# SH6_-_LOAD_MONITORING_1.net
KiCad netlist of a schematic drawn in Altium Designer
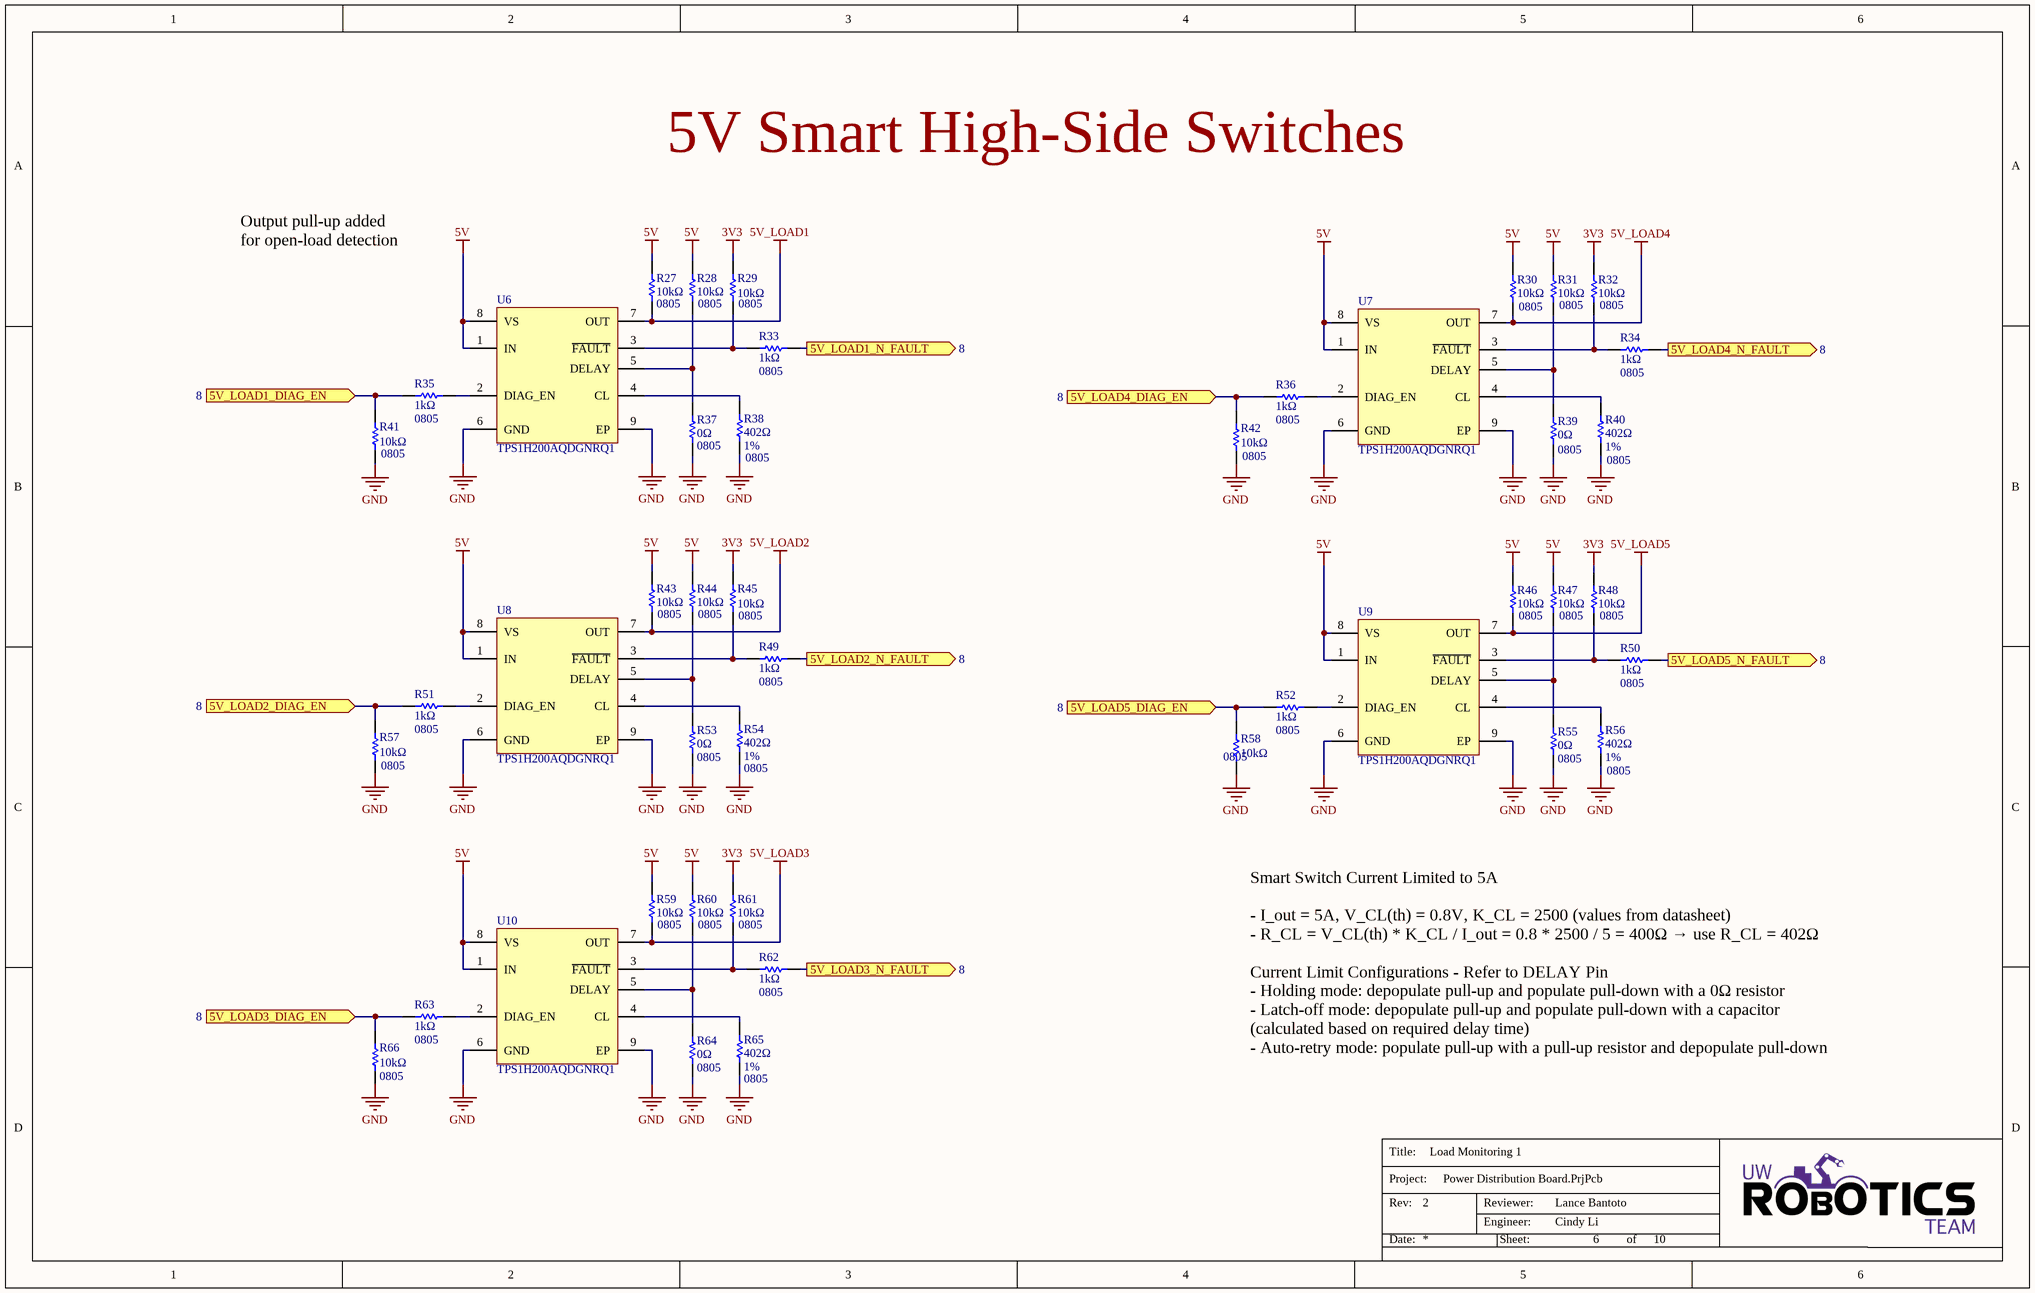
[diagram p0: SH6 - LOAD MONITORING 1.SchDoc]

(export (version "E")
  (design (tool "Eeschema 10.0.6"))
  (components
    (comp (ref "R27")
      (value "10kΩ")
      (footprint "RESC0805")
      (description "RES 10K OHM 5% 1/8W 0805")
      (fields
        (field (name "LCSC PART #") "C17414")
        (field (name "PACKAGE/FOOTPRINT") "0805")
        (field (name "Comment") "RES_10kΩ_0805_5%")
      )
      (libsource (lib "UWRT_Schematic_Library_2020") (part "RES_10kΩ_0805_5%"))
    )
    (comp (ref "R28")
      (value "10kΩ")
      (footprint "RESC0805")
      (description "RES 10K OHM 5% 1/8W 0805")
      (fields
        (field (name "LCSC PART #") "C17414")
        (field (name "PACKAGE/FOOTPRINT") "0805")
        (field (name "Comment") "RES_10kΩ_0805_5%")
      )
      (libsource (lib "UWRT_Schematic_Library_2020") (part "RES_10kΩ_0805_5%"))
    )
    (comp (ref "R29")
      (value "10kΩ")
      (footprint "RESC0805")
      (description "RES 10K OHM 5% 1/8W 0805")
      (fields
        (field (name "LCSC PART #") "C17414")
        (field (name "PACKAGE/FOOTPRINT") "0805")
        (field (name "Comment") "RES_10kΩ_0805_5%")
      )
      (libsource (lib "UWRT_Schematic_Library_2020") (part "RES_10kΩ_0805_5%"))
    )
    (comp (ref "R30")
      (value "10kΩ")
      (footprint "RESC0805")
      (description "RES 10K OHM 5% 1/8W 0805")
      (fields
        (field (name "LCSC PART #") "C17414")
        (field (name "PACKAGE/FOOTPRINT") "0805")
        (field (name "Comment") "RES_10kΩ_0805_5%")
      )
      (libsource (lib "UWRT_Schematic_Library_2020") (part "RES_10kΩ_0805_5%"))
    )
    (comp (ref "R31")
      (value "10kΩ")
      (footprint "RESC0805")
      (description "RES 10K OHM 5% 1/8W 0805")
      (fields
        (field (name "LCSC PART #") "C17414")
        (field (name "PACKAGE/FOOTPRINT") "0805")
        (field (name "Comment") "RES_10kΩ_0805_5%")
      )
      (libsource (lib "UWRT_Schematic_Library_2020") (part "RES_10kΩ_0805_5%"))
    )
    (comp (ref "R32")
      (value "10kΩ")
      (footprint "RESC0805")
      (description "RES 10K OHM 5% 1/8W 0805")
      (fields
        (field (name "LCSC PART #") "C17414")
        (field (name "PACKAGE/FOOTPRINT") "0805")
        (field (name "Comment") "RES_10kΩ_0805_5%")
      )
      (libsource (lib "UWRT_Schematic_Library_2020") (part "RES_10kΩ_0805_5%"))
    )
    (comp (ref "R33")
      (value "RES_1kΩ_0805_1%")
      (footprint "RESC0805")
      (description "RES 1K OHM 1% 1/8W 0805")
      (fields
        (field (name "TOLERANCE") "1%")
        (field (name "RESISTANCE") "1kΩ")
        (field (name "LCSC PART #") "C17513")
        (field (name "PACKAGE/FOOTPRINT") "0805")
      )
      (libsource (lib "UWRT_Schematic_Library_2020") (part "RES_1kΩ_0805_1%"))
    )
    (comp (ref "R34")
      (value "RES_1kΩ_0805_1%")
      (footprint "RESC0805")
      (description "RES 1K OHM 1% 1/8W 0805")
      (fields
        (field (name "TOLERANCE") "1%")
        (field (name "RESISTANCE") "1kΩ")
        (field (name "LCSC PART #") "C17513")
        (field (name "PACKAGE/FOOTPRINT") "0805")
      )
      (libsource (lib "UWRT_Schematic_Library_2020") (part "RES_1kΩ_0805_1%"))
    )
    (comp (ref "R35")
      (value "RES_1kΩ_0805_1%")
      (footprint "RESC0805")
      (description "RES 1K OHM 1% 1/8W 0805")
      (fields
        (field (name "TOLERANCE") "1%")
        (field (name "RESISTANCE") "1kΩ")
        (field (name "LCSC PART #") "C17513")
        (field (name "PACKAGE/FOOTPRINT") "0805")
      )
      (libsource (lib "UWRT_Schematic_Library_2020") (part "RES_1kΩ_0805_1%"))
    )
    (comp (ref "R36")
      (value "RES_1kΩ_0805_1%")
      (footprint "RESC0805")
      (description "RES 1K OHM 1% 1/8W 0805")
      (fields
        (field (name "TOLERANCE") "1%")
        (field (name "RESISTANCE") "1kΩ")
        (field (name "LCSC PART #") "C17513")
        (field (name "PACKAGE/FOOTPRINT") "0805")
      )
      (libsource (lib "UWRT_Schematic_Library_2020") (part "RES_1kΩ_0805_1%"))
    )
    (comp (ref "R37")
      (value "0Ω")
      (footprint "RESC0805")
      (description "RES 0 OHM JUMPER 1/8W 0805")
      (fields
        (field (name "LCSC PART #") "C17477")
        (field (name "PACKAGE/FOOTPRINT") "0805")
        (field (name "Comment") "RES_0Ω_0805")
      )
      (libsource (lib "UWRT_Schematic_Library_2020") (part "RES_0Ω_0805"))
    )
    (comp (ref "R38")
      (value "402Ω")
      (footprint "RESC0805")
      (description "RES 402 OHM 1% 1/8W 0805")
      (fields
        (field (name "TOLERANCE") "1%")
        (field (name "LCSC PART #") "C17681")
        (field (name "PACKAGE/FOOTPRINT") "0805")
        (field (name "Comment") "RES_402Ω_0805_1%")
      )
      (libsource (lib "UWRT_Schematic_Library_2020") (part "RES_402Ω_0805_1%"))
    )
    (comp (ref "R39")
      (value "0Ω")
      (footprint "RESC0805")
      (description "RES 0 OHM JUMPER 1/8W 0805")
      (fields
        (field (name "LCSC PART #") "C17477")
        (field (name "PACKAGE/FOOTPRINT") "0805")
        (field (name "Comment") "RES_0Ω_0805")
      )
      (libsource (lib "UWRT_Schematic_Library_2020") (part "RES_0Ω_0805"))
    )
    (comp (ref "R40")
      (value "402Ω")
      (footprint "RESC0805")
      (description "RES 402 OHM 1% 1/8W 0805")
      (fields
        (field (name "TOLERANCE") "1%")
        (field (name "LCSC PART #") "C17681")
        (field (name "PACKAGE/FOOTPRINT") "0805")
        (field (name "Comment") "RES_402Ω_0805_1%")
      )
      (libsource (lib "UWRT_Schematic_Library_2020") (part "RES_402Ω_0805_1%"))
    )
    (comp (ref "R41")
      (value "10kΩ")
      (footprint "RESC0805")
      (description "RES 10K OHM 5% 1/8W 0805")
      (fields
        (field (name "LCSC PART #") "C17414")
        (field (name "PACKAGE/FOOTPRINT") "0805")
        (field (name "Comment") "RES_10kΩ_0805_5%")
      )
      (libsource (lib "UWRT_Schematic_Library_2020") (part "RES_10kΩ_0805_5%"))
    )
    (comp (ref "R42")
      (value "10kΩ")
      (footprint "RESC0805")
      (description "RES 10K OHM 5% 1/8W 0805")
      (fields
        (field (name "LCSC PART #") "C17414")
        (field (name "PACKAGE/FOOTPRINT") "0805")
        (field (name "Comment") "RES_10kΩ_0805_5%")
      )
      (libsource (lib "UWRT_Schematic_Library_2020") (part "RES_10kΩ_0805_5%"))
    )
    (comp (ref "R43")
      (value "10kΩ")
      (footprint "RESC0805")
      (description "RES 10K OHM 5% 1/8W 0805")
      (fields
        (field (name "LCSC PART #") "C17414")
        (field (name "PACKAGE/FOOTPRINT") "0805")
        (field (name "Comment") "RES_10kΩ_0805_5%")
      )
      (libsource (lib "UWRT_Schematic_Library_2020") (part "RES_10kΩ_0805_5%"))
    )
    (comp (ref "R44")
      (value "10kΩ")
      (footprint "RESC0805")
      (description "RES 10K OHM 5% 1/8W 0805")
      (fields
        (field (name "LCSC PART #") "C17414")
        (field (name "PACKAGE/FOOTPRINT") "0805")
        (field (name "Comment") "RES_10kΩ_0805_5%")
      )
      (libsource (lib "UWRT_Schematic_Library_2020") (part "RES_10kΩ_0805_5%"))
    )
    (comp (ref "R45")
      (value "10kΩ")
      (footprint "RESC0805")
      (description "RES 10K OHM 5% 1/8W 0805")
      (fields
        (field (name "LCSC PART #") "C17414")
        (field (name "PACKAGE/FOOTPRINT") "0805")
        (field (name "Comment") "RES_10kΩ_0805_5%")
      )
      (libsource (lib "UWRT_Schematic_Library_2020") (part "RES_10kΩ_0805_5%"))
    )
    (comp (ref "R46")
      (value "10kΩ")
      (footprint "RESC0805")
      (description "RES 10K OHM 5% 1/8W 0805")
      (fields
        (field (name "LCSC PART #") "C17414")
        (field (name "PACKAGE/FOOTPRINT") "0805")
        (field (name "Comment") "RES_10kΩ_0805_5%")
      )
      (libsource (lib "UWRT_Schematic_Library_2020") (part "RES_10kΩ_0805_5%"))
    )
    (comp (ref "R47")
      (value "10kΩ")
      (footprint "RESC0805")
      (description "RES 10K OHM 5% 1/8W 0805")
      (fields
        (field (name "LCSC PART #") "C17414")
        (field (name "PACKAGE/FOOTPRINT") "0805")
        (field (name "Comment") "RES_10kΩ_0805_5%")
      )
      (libsource (lib "UWRT_Schematic_Library_2020") (part "RES_10kΩ_0805_5%"))
    )
    (comp (ref "R48")
      (value "10kΩ")
      (footprint "RESC0805")
      (description "RES 10K OHM 5% 1/8W 0805")
      (fields
        (field (name "LCSC PART #") "C17414")
        (field (name "PACKAGE/FOOTPRINT") "0805")
        (field (name "Comment") "RES_10kΩ_0805_5%")
      )
      (libsource (lib "UWRT_Schematic_Library_2020") (part "RES_10kΩ_0805_5%"))
    )
    (comp (ref "R49")
      (value "RES_1kΩ_0805_1%")
      (footprint "RESC0805")
      (description "RES 1K OHM 1% 1/8W 0805")
      (fields
        (field (name "TOLERANCE") "1%")
        (field (name "RESISTANCE") "1kΩ")
        (field (name "LCSC PART #") "C17513")
        (field (name "PACKAGE/FOOTPRINT") "0805")
      )
      (libsource (lib "UWRT_Schematic_Library_2020") (part "RES_1kΩ_0805_1%"))
    )
    (comp (ref "R50")
      (value "RES_1kΩ_0805_1%")
      (footprint "RESC0805")
      (description "RES 1K OHM 1% 1/8W 0805")
      (fields
        (field (name "TOLERANCE") "1%")
        (field (name "RESISTANCE") "1kΩ")
        (field (name "LCSC PART #") "C17513")
        (field (name "PACKAGE/FOOTPRINT") "0805")
      )
      (libsource (lib "UWRT_Schematic_Library_2020") (part "RES_1kΩ_0805_1%"))
    )
    (comp (ref "R51")
      (value "RES_1kΩ_0805_1%")
      (footprint "RESC0805")
      (description "RES 1K OHM 1% 1/8W 0805")
      (fields
        (field (name "TOLERANCE") "1%")
        (field (name "RESISTANCE") "1kΩ")
        (field (name "LCSC PART #") "C17513")
        (field (name "PACKAGE/FOOTPRINT") "0805")
      )
      (libsource (lib "UWRT_Schematic_Library_2020") (part "RES_1kΩ_0805_1%"))
    )
    (comp (ref "R52")
      (value "RES_1kΩ_0805_1%")
      (footprint "RESC0805")
      (description "RES 1K OHM 1% 1/8W 0805")
      (fields
        (field (name "TOLERANCE") "1%")
        (field (name "RESISTANCE") "1kΩ")
        (field (name "LCSC PART #") "C17513")
        (field (name "PACKAGE/FOOTPRINT") "0805")
      )
      (libsource (lib "UWRT_Schematic_Library_2020") (part "RES_1kΩ_0805_1%"))
    )
    (comp (ref "R53")
      (value "0Ω")
      (footprint "RESC0805")
      (description "RES 0 OHM JUMPER 1/8W 0805")
      (fields
        (field (name "LCSC PART #") "C17477")
        (field (name "PACKAGE/FOOTPRINT") "0805")
        (field (name "Comment") "RES_0Ω_0805")
      )
      (libsource (lib "UWRT_Schematic_Library_2020") (part "RES_0Ω_0805"))
    )
    (comp (ref "R54")
      (value "402Ω")
      (footprint "RESC0805")
      (description "RES 402 OHM 1% 1/8W 0805")
      (fields
        (field (name "TOLERANCE") "1%")
        (field (name "LCSC PART #") "C17681")
        (field (name "PACKAGE/FOOTPRINT") "0805")
        (field (name "Comment") "RES_402Ω_0805_1%")
      )
      (libsource (lib "UWRT_Schematic_Library_2020") (part "RES_402Ω_0805_1%"))
    )
    (comp (ref "R55")
      (value "0Ω")
      (footprint "RESC0805")
      (description "RES 0 OHM JUMPER 1/8W 0805")
      (fields
        (field (name "LCSC PART #") "C17477")
        (field (name "PACKAGE/FOOTPRINT") "0805")
        (field (name "Comment") "RES_0Ω_0805")
      )
      (libsource (lib "UWRT_Schematic_Library_2020") (part "RES_0Ω_0805"))
    )
    (comp (ref "R56")
      (value "402Ω")
      (footprint "RESC0805")
      (description "RES 402 OHM 1% 1/8W 0805")
      (fields
        (field (name "TOLERANCE") "1%")
        (field (name "LCSC PART #") "C17681")
        (field (name "PACKAGE/FOOTPRINT") "0805")
        (field (name "Comment") "RES_402Ω_0805_1%")
      )
      (libsource (lib "UWRT_Schematic_Library_2020") (part "RES_402Ω_0805_1%"))
    )
    (comp (ref "R57")
      (value "10kΩ")
      (footprint "RESC0805")
      (description "RES 10K OHM 5% 1/8W 0805")
      (fields
        (field (name "LCSC PART #") "C17414")
        (field (name "PACKAGE/FOOTPRINT") "0805")
        (field (name "Comment") "RES_10kΩ_0805_5%")
      )
      (libsource (lib "UWRT_Schematic_Library_2020") (part "RES_10kΩ_0805_5%"))
    )
    (comp (ref "R58")
      (value "10kΩ")
      (footprint "RESC0805")
      (description "RES 10K OHM 5% 1/8W 0805")
      (fields
        (field (name "LCSC PART #") "C17414")
        (field (name "PACKAGE/FOOTPRINT") "0805")
        (field (name "Comment") "RES_10kΩ_0805_5%")
      )
      (libsource (lib "UWRT_Schematic_Library_2020") (part "RES_10kΩ_0805_5%"))
    )
    (comp (ref "R59")
      (value "10kΩ")
      (footprint "RESC0805")
      (description "RES 10K OHM 5% 1/8W 0805")
      (fields
        (field (name "LCSC PART #") "C17414")
        (field (name "PACKAGE/FOOTPRINT") "0805")
        (field (name "Comment") "RES_10kΩ_0805_5%")
      )
      (libsource (lib "UWRT_Schematic_Library_2020") (part "RES_10kΩ_0805_5%"))
    )
    (comp (ref "R60")
      (value "10kΩ")
      (footprint "RESC0805")
      (description "RES 10K OHM 5% 1/8W 0805")
      (fields
        (field (name "LCSC PART #") "C17414")
        (field (name "PACKAGE/FOOTPRINT") "0805")
        (field (name "Comment") "RES_10kΩ_0805_5%")
      )
      (libsource (lib "UWRT_Schematic_Library_2020") (part "RES_10kΩ_0805_5%"))
    )
    (comp (ref "R61")
      (value "10kΩ")
      (footprint "RESC0805")
      (description "RES 10K OHM 5% 1/8W 0805")
      (fields
        (field (name "LCSC PART #") "C17414")
        (field (name "PACKAGE/FOOTPRINT") "0805")
        (field (name "Comment") "RES_10kΩ_0805_5%")
      )
      (libsource (lib "UWRT_Schematic_Library_2020") (part "RES_10kΩ_0805_5%"))
    )
    (comp (ref "R62")
      (value "RES_1kΩ_0805_1%")
      (footprint "RESC0805")
      (description "RES 1K OHM 1% 1/8W 0805")
      (fields
        (field (name "TOLERANCE") "1%")
        (field (name "RESISTANCE") "1kΩ")
        (field (name "LCSC PART #") "C17513")
        (field (name "PACKAGE/FOOTPRINT") "0805")
      )
      (libsource (lib "UWRT_Schematic_Library_2020") (part "RES_1kΩ_0805_1%"))
    )
    (comp (ref "R63")
      (value "RES_1kΩ_0805_1%")
      (footprint "RESC0805")
      (description "RES 1K OHM 1% 1/8W 0805")
      (fields
        (field (name "TOLERANCE") "1%")
        (field (name "RESISTANCE") "1kΩ")
        (field (name "LCSC PART #") "C17513")
        (field (name "PACKAGE/FOOTPRINT") "0805")
      )
      (libsource (lib "UWRT_Schematic_Library_2020") (part "RES_1kΩ_0805_1%"))
    )
    (comp (ref "R64")
      (value "0Ω")
      (footprint "RESC0805")
      (description "RES 0 OHM JUMPER 1/8W 0805")
      (fields
        (field (name "LCSC PART #") "C17477")
        (field (name "PACKAGE/FOOTPRINT") "0805")
        (field (name "Comment") "RES_0Ω_0805")
      )
      (libsource (lib "UWRT_Schematic_Library_2020") (part "RES_0Ω_0805"))
    )
    (comp (ref "R65")
      (value "402Ω")
      (footprint "RESC0805")
      (description "RES 402 OHM 1% 1/8W 0805")
      (fields
        (field (name "TOLERANCE") "1%")
        (field (name "LCSC PART #") "C17681")
        (field (name "PACKAGE/FOOTPRINT") "0805")
        (field (name "Comment") "RES_402Ω_0805_1%")
      )
      (libsource (lib "UWRT_Schematic_Library_2020") (part "RES_402Ω_0805_1%"))
    )
    (comp (ref "R66")
      (value "10kΩ")
      (footprint "RESC0805")
      (description "RES 10K OHM 5% 1/8W 0805")
      (fields
        (field (name "LCSC PART #") "C17414")
        (field (name "PACKAGE/FOOTPRINT") "0805")
        (field (name "Comment") "RES_10kΩ_0805_5%")
      )
      (libsource (lib "UWRT_Schematic_Library_2020") (part "RES_10kΩ_0805_5%"))
    )
    (comp (ref "U6")
      (value "TPS1H200A-Q1")
      (footprint "DGN0008G")
      (description "IC PWR DRIVER N-CHAN 1:1 8MSOP")
      (fields (field (name "MANUFACTURER PART NUMBER 1") "TPS1H200AQDGNRQ1"))
      (libsource (lib "UWRT_Schematic_Library_2020") (part "TPS1H200A-Q1"))
    )
    (comp (ref "U7")
      (value "TPS1H200A-Q1")
      (footprint "DGN0008G")
      (description "IC PWR DRIVER N-CHAN 1:1 8MSOP")
      (fields (field (name "MANUFACTURER PART NUMBER 1") "TPS1H200AQDGNRQ1"))
      (libsource (lib "UWRT_Schematic_Library_2020") (part "TPS1H200A-Q1"))
    )
    (comp (ref "U8")
      (value "TPS1H200A-Q1")
      (footprint "DGN0008G")
      (description "IC PWR DRIVER N-CHAN 1:1 8MSOP")
      (fields (field (name "MANUFACTURER PART NUMBER 1") "TPS1H200AQDGNRQ1"))
      (libsource (lib "UWRT_Schematic_Library_2020") (part "TPS1H200A-Q1"))
    )
    (comp (ref "U9")
      (value "TPS1H200A-Q1")
      (footprint "DGN0008G")
      (description "IC PWR DRIVER N-CHAN 1:1 8MSOP")
      (fields (field (name "MANUFACTURER PART NUMBER 1") "TPS1H200AQDGNRQ1"))
      (libsource (lib "UWRT_Schematic_Library_2020") (part "TPS1H200A-Q1"))
    )
    (comp (ref "U10")
      (value "TPS1H200A-Q1")
      (footprint "DGN0008G")
      (description "IC PWR DRIVER N-CHAN 1:1 8MSOP")
      (fields (field (name "MANUFACTURER PART NUMBER 1") "TPS1H200AQDGNRQ1"))
      (libsource (lib "UWRT_Schematic_Library_2020") (part "TPS1H200A-Q1"))
    )
  )
  (nets
    (net (code "1") (name "/5V_LOAD1_DIAG_EN") (class "Default")
      (node (ref "R35") (pin "1") (pinfunction "1_1") (pintype "passive"))
      (node (ref "R41") (pin "2") (pinfunction "2_2") (pintype "passive"))
    )
    (net (code "2") (name "/5V_LOAD1_N_FAULT") (class "Default")
      (node (ref "R33") (pin "2") (pinfunction "2_2") (pintype "passive"))
    )
    (net (code "3") (name "/5V_LOAD2_DIAG_EN") (class "Default")
      (node (ref "R51") (pin "1") (pinfunction "1_1") (pintype "passive"))
      (node (ref "R57") (pin "2") (pinfunction "2_2") (pintype "passive"))
    )
    (net (code "4") (name "/5V_LOAD2_N_FAULT") (class "Default")
      (node (ref "R49") (pin "2") (pinfunction "2_2") (pintype "passive"))
    )
    (net (code "5") (name "/5V_LOAD3_DIAG_EN") (class "Default")
      (node (ref "R63") (pin "1") (pinfunction "1_1") (pintype "passive"))
      (node (ref "R66") (pin "2") (pinfunction "2_2") (pintype "passive"))
    )
    (net (code "6") (name "/5V_LOAD3_N_FAULT") (class "Default")
      (node (ref "R62") (pin "2") (pinfunction "2_2") (pintype "passive"))
    )
    (net (code "7") (name "/5V_LOAD4_DIAG_EN") (class "Default")
      (node (ref "R36") (pin "1") (pinfunction "1_1") (pintype "passive"))
      (node (ref "R42") (pin "2") (pinfunction "2_2") (pintype "passive"))
    )
    (net (code "8") (name "/5V_LOAD4_N_FAULT") (class "Default")
      (node (ref "R34") (pin "2") (pinfunction "2_2") (pintype "passive"))
    )
    (net (code "9") (name "/5V_LOAD5_DIAG_EN") (class "Default")
      (node (ref "R52") (pin "1") (pinfunction "1_1") (pintype "passive"))
      (node (ref "R58") (pin "2") (pinfunction "2_2") (pintype "passive"))
    )
    (net (code "10") (name "/5V_LOAD5_N_FAULT") (class "Default")
      (node (ref "R50") (pin "2") (pinfunction "2_2") (pintype "passive"))
    )
    (net (code "11") (name "3V3") (class "Default")
      (node (ref "R29") (pin "2") (pinfunction "2_2") (pintype "passive"))
      (node (ref "R32") (pin "2") (pinfunction "2_2") (pintype "passive"))
      (node (ref "R45") (pin "2") (pinfunction "2_2") (pintype "passive"))
      (node (ref "R48") (pin "2") (pinfunction "2_2") (pintype "passive"))
      (node (ref "R61") (pin "2") (pinfunction "2_2") (pintype "passive"))
    )
    (net (code "12") (name "5V") (class "Default")
      (node (ref "R27") (pin "2") (pinfunction "2_2") (pintype "passive"))
      (node (ref "R28") (pin "2") (pinfunction "2_2") (pintype "passive"))
      (node (ref "R30") (pin "2") (pinfunction "2_2") (pintype "passive"))
      (node (ref "R31") (pin "2") (pinfunction "2_2") (pintype "passive"))
      (node (ref "R43") (pin "2") (pinfunction "2_2") (pintype "passive"))
      (node (ref "R44") (pin "2") (pinfunction "2_2") (pintype "passive"))
      (node (ref "R46") (pin "2") (pinfunction "2_2") (pintype "passive"))
      (node (ref "R47") (pin "2") (pinfunction "2_2") (pintype "passive"))
      (node (ref "R59") (pin "2") (pinfunction "2_2") (pintype "passive"))
      (node (ref "R60") (pin "2") (pinfunction "2_2") (pintype "passive"))
      (node (ref "U10") (pin "1") (pinfunction "IN_1") (pintype "passive"))
      (node (ref "U10") (pin "8") (pinfunction "VS_8") (pintype "passive"))
      (node (ref "U6") (pin "1") (pinfunction "IN_1") (pintype "passive"))
      (node (ref "U6") (pin "8") (pinfunction "VS_8") (pintype "passive"))
      (node (ref "U7") (pin "1") (pinfunction "IN_1") (pintype "passive"))
      (node (ref "U7") (pin "8") (pinfunction "VS_8") (pintype "passive"))
      (node (ref "U8") (pin "1") (pinfunction "IN_1") (pintype "passive"))
      (node (ref "U8") (pin "8") (pinfunction "VS_8") (pintype "passive"))
      (node (ref "U9") (pin "1") (pinfunction "IN_1") (pintype "passive"))
      (node (ref "U9") (pin "8") (pinfunction "VS_8") (pintype "passive"))
    )
    (net (code "13") (name "5V_LOAD1") (class "Default")
      (node (ref "R27") (pin "1") (pinfunction "1_1") (pintype "passive"))
      (node (ref "U6") (pin "7") (pinfunction "OUT_7") (pintype "passive"))
    )
    (net (code "14") (name "5V_LOAD2") (class "Default")
      (node (ref "R43") (pin "1") (pinfunction "1_1") (pintype "passive"))
      (node (ref "U8") (pin "7") (pinfunction "OUT_7") (pintype "passive"))
    )
    (net (code "15") (name "5V_LOAD3") (class "Default")
      (node (ref "R59") (pin "1") (pinfunction "1_1") (pintype "passive"))
      (node (ref "U10") (pin "7") (pinfunction "OUT_7") (pintype "passive"))
    )
    (net (code "16") (name "5V_LOAD4") (class "Default")
      (node (ref "R30") (pin "1") (pinfunction "1_1") (pintype "passive"))
      (node (ref "U7") (pin "7") (pinfunction "OUT_7") (pintype "passive"))
    )
    (net (code "17") (name "5V_LOAD5") (class "Default")
      (node (ref "R46") (pin "1") (pinfunction "1_1") (pintype "passive"))
      (node (ref "U9") (pin "7") (pinfunction "OUT_7") (pintype "passive"))
    )
    (net (code "18") (name "GND") (class "Default")
      (node (ref "R37") (pin "1") (pinfunction "1_1") (pintype "passive"))
      (node (ref "R38") (pin "1") (pinfunction "1_1") (pintype "passive"))
      (node (ref "R39") (pin "1") (pinfunction "1_1") (pintype "passive"))
      (node (ref "R40") (pin "1") (pinfunction "1_1") (pintype "passive"))
      (node (ref "R41") (pin "1") (pinfunction "1_1") (pintype "passive"))
      (node (ref "R42") (pin "1") (pinfunction "1_1") (pintype "passive"))
      (node (ref "R53") (pin "1") (pinfunction "1_1") (pintype "passive"))
      (node (ref "R54") (pin "1") (pinfunction "1_1") (pintype "passive"))
      (node (ref "R55") (pin "1") (pinfunction "1_1") (pintype "passive"))
      (node (ref "R56") (pin "1") (pinfunction "1_1") (pintype "passive"))
      (node (ref "R57") (pin "1") (pinfunction "1_1") (pintype "passive"))
      (node (ref "R58") (pin "1") (pinfunction "1_1") (pintype "passive"))
      (node (ref "R64") (pin "1") (pinfunction "1_1") (pintype "passive"))
      (node (ref "R65") (pin "1") (pinfunction "1_1") (pintype "passive"))
      (node (ref "R66") (pin "1") (pinfunction "1_1") (pintype "passive"))
      (node (ref "U10") (pin "6") (pinfunction "GND_6") (pintype "passive"))
      (node (ref "U10") (pin "9") (pinfunction "EP_9") (pintype "passive"))
      (node (ref "U6") (pin "6") (pinfunction "GND_6") (pintype "passive"))
      (node (ref "U6") (pin "9") (pinfunction "EP_9") (pintype "passive"))
      (node (ref "U7") (pin "6") (pinfunction "GND_6") (pintype "passive"))
      (node (ref "U7") (pin "9") (pinfunction "EP_9") (pintype "passive"))
      (node (ref "U8") (pin "6") (pinfunction "GND_6") (pintype "passive"))
      (node (ref "U8") (pin "9") (pinfunction "EP_9") (pintype "passive"))
      (node (ref "U9") (pin "6") (pinfunction "GND_6") (pintype "passive"))
      (node (ref "U9") (pin "9") (pinfunction "EP_9") (pintype "passive"))
    )
    (net (code "19") (name "Net-(U6-CL)") (class "Default")
      (node (ref "R38") (pin "2") (pinfunction "2_2") (pintype "passive"))
      (node (ref "U6") (pin "4") (pinfunction "CL_4") (pintype "passive"))
    )
    (net (code "20") (name "Net-(U6-DELAY)") (class "Default")
      (node (ref "R28") (pin "1") (pinfunction "1_1") (pintype "passive"))
      (node (ref "R37") (pin "2") (pinfunction "2_2") (pintype "passive"))
      (node (ref "U6") (pin "5") (pinfunction "DELAY_5") (pintype "passive"))
    )
    (net (code "21") (name "Net-(U6-DIAG_EN)") (class "Default")
      (node (ref "R35") (pin "2") (pinfunction "2_2") (pintype "passive"))
      (node (ref "U6") (pin "2") (pinfunction "DIAG_EN_2") (pintype "passive"))
    )
    (net (code "22") (name "Net-(U6-~{FAULT})") (class "Default")
      (node (ref "R29") (pin "1") (pinfunction "1_1") (pintype "passive"))
      (node (ref "R33") (pin "1") (pinfunction "1_1") (pintype "passive"))
      (node (ref "U6") (pin "3") (pinfunction "~{FAULT}_3") (pintype "passive"))
    )
    (net (code "23") (name "Net-(U7-CL)") (class "Default")
      (node (ref "R40") (pin "2") (pinfunction "2_2") (pintype "passive"))
      (node (ref "U7") (pin "4") (pinfunction "CL_4") (pintype "passive"))
    )
    (net (code "24") (name "Net-(U7-DELAY)") (class "Default")
      (node (ref "R31") (pin "1") (pinfunction "1_1") (pintype "passive"))
      (node (ref "R39") (pin "2") (pinfunction "2_2") (pintype "passive"))
      (node (ref "U7") (pin "5") (pinfunction "DELAY_5") (pintype "passive"))
    )
    (net (code "25") (name "Net-(U7-DIAG_EN)") (class "Default")
      (node (ref "R36") (pin "2") (pinfunction "2_2") (pintype "passive"))
      (node (ref "U7") (pin "2") (pinfunction "DIAG_EN_2") (pintype "passive"))
    )
    (net (code "26") (name "Net-(U7-~{FAULT})") (class "Default")
      (node (ref "R32") (pin "1") (pinfunction "1_1") (pintype "passive"))
      (node (ref "R34") (pin "1") (pinfunction "1_1") (pintype "passive"))
      (node (ref "U7") (pin "3") (pinfunction "~{FAULT}_3") (pintype "passive"))
    )
    (net (code "27") (name "Net-(U8-CL)") (class "Default")
      (node (ref "R54") (pin "2") (pinfunction "2_2") (pintype "passive"))
      (node (ref "U8") (pin "4") (pinfunction "CL_4") (pintype "passive"))
    )
    (net (code "28") (name "Net-(U8-DELAY)") (class "Default")
      (node (ref "R44") (pin "1") (pinfunction "1_1") (pintype "passive"))
      (node (ref "R53") (pin "2") (pinfunction "2_2") (pintype "passive"))
      (node (ref "U8") (pin "5") (pinfunction "DELAY_5") (pintype "passive"))
    )
    (net (code "29") (name "Net-(U8-DIAG_EN)") (class "Default")
      (node (ref "R51") (pin "2") (pinfunction "2_2") (pintype "passive"))
      (node (ref "U8") (pin "2") (pinfunction "DIAG_EN_2") (pintype "passive"))
    )
    (net (code "30") (name "Net-(U8-~{FAULT})") (class "Default")
      (node (ref "R45") (pin "1") (pinfunction "1_1") (pintype "passive"))
      (node (ref "R49") (pin "1") (pinfunction "1_1") (pintype "passive"))
      (node (ref "U8") (pin "3") (pinfunction "~{FAULT}_3") (pintype "passive"))
    )
    (net (code "31") (name "Net-(U9-CL)") (class "Default")
      (node (ref "R56") (pin "2") (pinfunction "2_2") (pintype "passive"))
      (node (ref "U9") (pin "4") (pinfunction "CL_4") (pintype "passive"))
    )
    (net (code "32") (name "Net-(U9-DELAY)") (class "Default")
      (node (ref "R47") (pin "1") (pinfunction "1_1") (pintype "passive"))
      (node (ref "R55") (pin "2") (pinfunction "2_2") (pintype "passive"))
      (node (ref "U9") (pin "5") (pinfunction "DELAY_5") (pintype "passive"))
    )
    (net (code "33") (name "Net-(U9-DIAG_EN)") (class "Default")
      (node (ref "R52") (pin "2") (pinfunction "2_2") (pintype "passive"))
      (node (ref "U9") (pin "2") (pinfunction "DIAG_EN_2") (pintype "passive"))
    )
    (net (code "34") (name "Net-(U9-~{FAULT})") (class "Default")
      (node (ref "R48") (pin "1") (pinfunction "1_1") (pintype "passive"))
      (node (ref "R50") (pin "1") (pinfunction "1_1") (pintype "passive"))
      (node (ref "U9") (pin "3") (pinfunction "~{FAULT}_3") (pintype "passive"))
    )
    (net (code "35") (name "Net-(U10-CL)") (class "Default")
      (node (ref "R65") (pin "2") (pinfunction "2_2") (pintype "passive"))
      (node (ref "U10") (pin "4") (pinfunction "CL_4") (pintype "passive"))
    )
    (net (code "36") (name "Net-(U10-DELAY)") (class "Default")
      (node (ref "R60") (pin "1") (pinfunction "1_1") (pintype "passive"))
      (node (ref "R64") (pin "2") (pinfunction "2_2") (pintype "passive"))
      (node (ref "U10") (pin "5") (pinfunction "DELAY_5") (pintype "passive"))
    )
    (net (code "37") (name "Net-(U10-DIAG_EN)") (class "Default")
      (node (ref "R63") (pin "2") (pinfunction "2_2") (pintype "passive"))
      (node (ref "U10") (pin "2") (pinfunction "DIAG_EN_2") (pintype "passive"))
    )
    (net (code "38") (name "Net-(U10-~{FAULT})") (class "Default")
      (node (ref "R61") (pin "1") (pinfunction "1_1") (pintype "passive"))
      (node (ref "R62") (pin "1") (pinfunction "1_1") (pintype "passive"))
      (node (ref "U10") (pin "3") (pinfunction "~{FAULT}_3") (pintype "passive"))
    )
  )
)
